# Schematic_openbook_v56.net
KiCad netlist of a schematic drawn in EAGLE
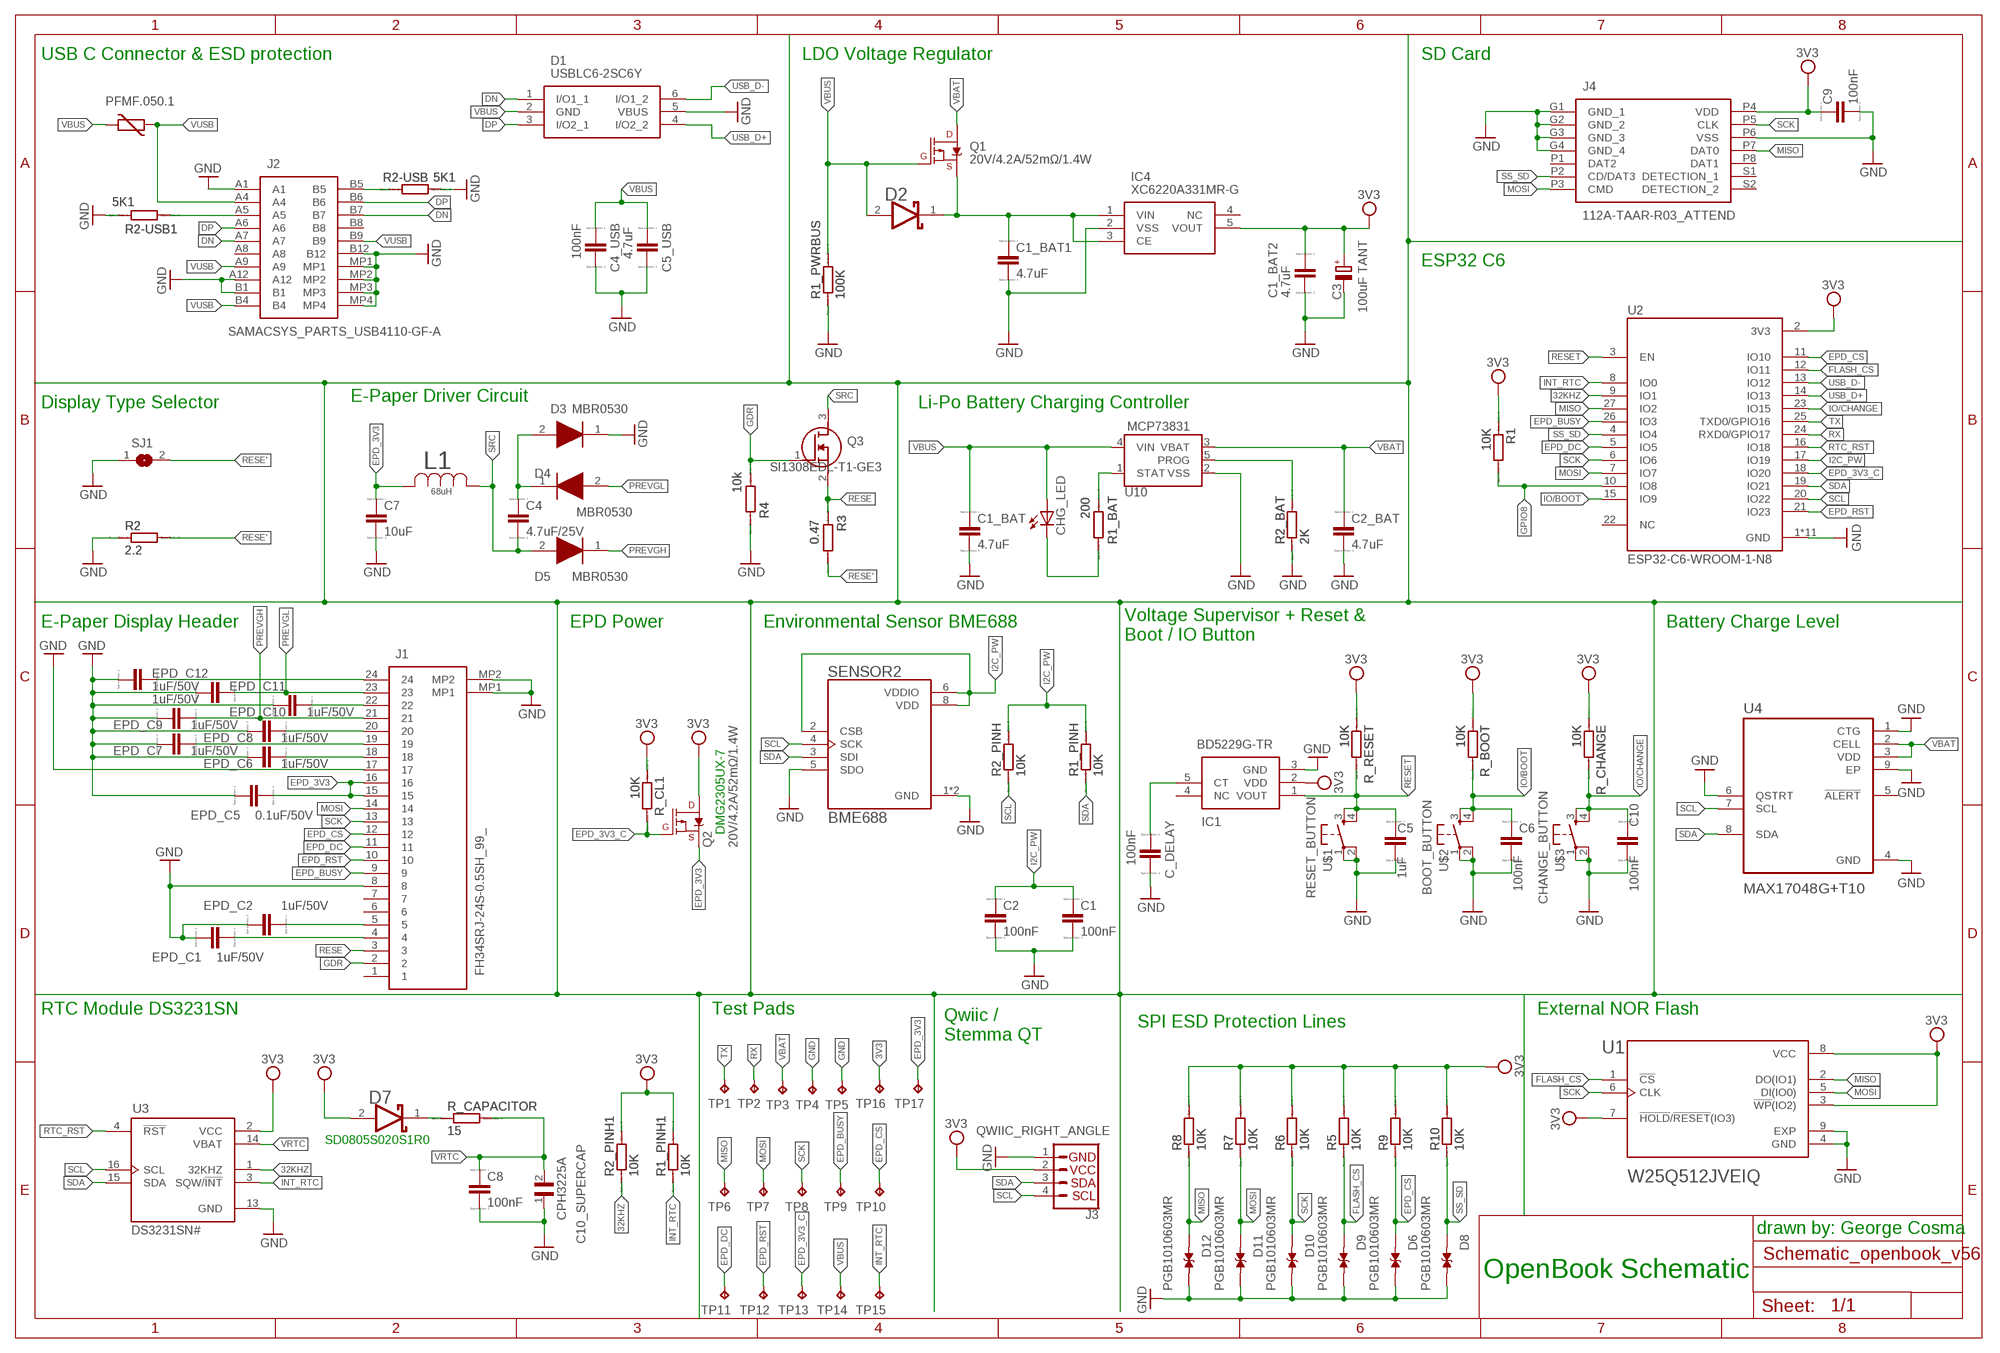
[diagram p0: schematic, sheet 1]

(export (version "E")
  (design (tool "Eeschema 10.0.6"))
  (components
    (comp (ref "C1")
      (value "100nF")
      (footprint "eagle-import:EAGLE-LTSPICE_C0402")
      (libsource (lib "eagle-import") (part "EAGLE-LTSPICE_CC0402"))
    )
    (comp (ref "C1_BAT")
      (value "4.7uF")
      (footprint "eagle-import:EAGLE-LTSPICE_C0402")
      (libsource (lib "eagle-import") (part "EAGLE-LTSPICE_CC0402"))
    )
    (comp (ref "C1_BAT1")
      (value "4.7uF")
      (footprint "eagle-import:EAGLE-LTSPICE_C0402")
      (libsource (lib "eagle-import") (part "EAGLE-LTSPICE_CC0402"))
    )
    (comp (ref "C1_BAT2")
      (value "4.7uF")
      (footprint "eagle-import:EAGLE-LTSPICE_C0402")
      (libsource (lib "eagle-import") (part "EAGLE-LTSPICE_CC0402"))
    )
    (comp (ref "C2")
      (value "100nF")
      (footprint "eagle-import:EAGLE-LTSPICE_C0402")
      (libsource (lib "eagle-import") (part "EAGLE-LTSPICE_CC0402"))
    )
    (comp (ref "C2_BAT")
      (value "4.7uF")
      (footprint "eagle-import:EAGLE-LTSPICE_C0402")
      (libsource (lib "eagle-import") (part "EAGLE-LTSPICE_CC0402"))
    )
    (comp (ref "C3")
      (value "100uF TANT")
      (footprint "eagle-import:RCL_CT3528")
      (libsource (lib "eagle-import") (part "RCL_CPOL-EUCT3528"))
    )
    (comp (ref "C4")
      (value "4.7uF/25V")
      (footprint "eagle-import:EAGLE-LTSPICE_C0402")
      (libsource (lib "eagle-import") (part "EAGLE-LTSPICE_CC0402"))
    )
    (comp (ref "C4_USB")
      (value "100nF")
      (footprint "eagle-import:EAGLE-LTSPICE_C0402")
      (libsource (lib "eagle-import") (part "EAGLE-LTSPICE_CC0402"))
    )
    (comp (ref "C5")
      (value "1uF")
      (footprint "eagle-import:EAGLE-LTSPICE_C0402")
      (libsource (lib "eagle-import") (part "EAGLE-LTSPICE_CC0402"))
    )
    (comp (ref "C5_USB")
      (value "4.7uF")
      (footprint "eagle-import:EAGLE-LTSPICE_C0402")
      (libsource (lib "eagle-import") (part "EAGLE-LTSPICE_CC0402"))
    )
    (comp (ref "C6")
      (value "100nF")
      (footprint "eagle-import:EAGLE-LTSPICE_C0402")
      (libsource (lib "eagle-import") (part "EAGLE-LTSPICE_CC0402"))
    )
    (comp (ref "C7")
      (value "10uF")
      (footprint "eagle-import:EAGLE-LTSPICE_C0402")
      (libsource (lib "eagle-import") (part "EAGLE-LTSPICE_CC0402"))
    )
    (comp (ref "C8")
      (value "100nF")
      (footprint "eagle-import:EAGLE-LTSPICE_C0402")
      (libsource (lib "eagle-import") (part "EAGLE-LTSPICE_CC0402"))
    )
    (comp (ref "C9")
      (value "100nF")
      (footprint "eagle-import:EAGLE-LTSPICE_C0402")
      (libsource (lib "eagle-import") (part "EAGLE-LTSPICE_CC0402"))
    )
    (comp (ref "C10")
      (value "100nF")
      (footprint "eagle-import:EAGLE-LTSPICE_C0402")
      (libsource (lib "eagle-import") (part "EAGLE-LTSPICE_CC0402"))
    )
    (comp (ref "C10_SUPERCAP")
      (value "CPH3225A")
      (footprint "eagle-import:CAPCP3225X100N")
      (fields (field (name "MF") "Seiko Instruments"))
      (libsource (lib "eagle-import") (part "CPH3225A"))
    )
    (comp (ref "CHG_LED")
      (value "ADAFRUIT_LEDCHIP-LED0603")
      (footprint "eagle-import:ADAFRUIT_CHIP-LED0603")
      (libsource (lib "eagle-import") (part "ADAFRUIT_LEDCHIP-LED0603"))
    )
    (comp (ref "C_DELAY")
      (value "100nF")
      (footprint "eagle-import:EAGLE-LTSPICE_C0402")
      (libsource (lib "eagle-import") (part "EAGLE-LTSPICE_CC0402"))
    )
    (comp (ref "D1")
      (value "USBLC6-2SC6Y")
      (footprint "eagle-import:SOT95P280X145-6N")
      (fields (field (name "MF") "STMicroelectronics"))
      (libsource (lib "eagle-import") (part "USBLC6-2SC6Y"))
    )
    (comp (ref "D2")
      (value "ESP32_WROVER_AVX---SD0805S020S1R0_AVX_SD0805S020S1R0_0_0AVX_SD0805S020S1R0_0_0")
      (footprint "eagle-import:ESP32_WROVER_AVX---SD0805S020S1R0_AVX_SD0805S020S1R0_0")
      (fields
        (field (name "DIGIKEY_PART_NUMBER") "478-7800-1-ND")
        (field (name "MF") "AVX")
        (field (name "MOUSER_PART_NUMBER") "581-SD0805S020S1R0")
      )
      (libsource (lib "eagle-import") (part "ESP32_WROVER_AVX---SD0805S020S1R0_AVX_SD0805S020S1R0_0_0AVX_SD0805S020S1R0_0_0"))
    )
    (comp (ref "D3")
      (value "MBR0530")
      (footprint "eagle-import:SOD3716X135N")
      (fields (field (name "MF") "ON Semiconductor"))
      (libsource (lib "eagle-import") (part "MBR0530"))
    )
    (comp (ref "D4")
      (value "MBR0530")
      (footprint "eagle-import:SOD3716X135N")
      (fields (field (name "MF") "ON Semiconductor"))
      (libsource (lib "eagle-import") (part "MBR0530"))
    )
    (comp (ref "D5")
      (value "MBR0530")
      (footprint "eagle-import:SOD3716X135N")
      (fields (field (name "MF") "ON Semiconductor"))
      (libsource (lib "eagle-import") (part "MBR0530"))
    )
    (comp (ref "D6")
      (value "PGB1010603MR")
      (footprint "eagle-import:DIOC1608X36N")
      (fields (field (name "MF") "Littelfuse Inc."))
      (libsource (lib "eagle-import") (part "PGB1010603MR"))
    )
    (comp (ref "D7")
      (value "SD0805S020S1R0")
      (footprint "eagle-import:ESP32_WROVER_AVX---SD0805S020S1R0_AVX_SD0805S020S1R0_0")
      (fields
        (field (name "DIGIKEY_PART_NUMBER") "478-7800-1-ND")
        (field (name "MF") "AVX")
        (field (name "MOUSER_PART_NUMBER") "581-SD0805S020S1R0")
      )
      (libsource (lib "eagle-import") (part "ESP32_WROVER_AVX---SD0805S020S1R0_AVX_SD0805S020S1R0_0_0AVX_SD0805S020S1R0_0_0"))
    )
    (comp (ref "D8")
      (value "PGB1010603MR")
      (footprint "eagle-import:DIOC1608X36N")
      (fields (field (name "MF") "Littelfuse Inc."))
      (libsource (lib "eagle-import") (part "PGB1010603MR"))
    )
    (comp (ref "D9")
      (value "PGB1010603MR")
      (footprint "eagle-import:DIOC1608X36N")
      (fields (field (name "MF") "Littelfuse Inc."))
      (libsource (lib "eagle-import") (part "PGB1010603MR"))
    )
    (comp (ref "D10")
      (value "PGB1010603MR")
      (footprint "eagle-import:DIOC1608X36N")
      (fields (field (name "MF") "Littelfuse Inc."))
      (libsource (lib "eagle-import") (part "PGB1010603MR"))
    )
    (comp (ref "D11")
      (value "PGB1010603MR")
      (footprint "eagle-import:DIOC1608X36N")
      (fields (field (name "MF") "Littelfuse Inc."))
      (libsource (lib "eagle-import") (part "PGB1010603MR"))
    )
    (comp (ref "D12")
      (value "PGB1010603MR")
      (footprint "eagle-import:DIOC1608X36N")
      (fields (field (name "MF") "Littelfuse Inc."))
      (libsource (lib "eagle-import") (part "PGB1010603MR"))
    )
    (comp (ref "EPD_C1")
      (value "1uF/50V")
      (footprint "eagle-import:EAGLE-LTSPICE_C0402")
      (libsource (lib "eagle-import") (part "EAGLE-LTSPICE_CC0402"))
    )
    (comp (ref "EPD_C2")
      (value "1uF/50V")
      (footprint "eagle-import:EAGLE-LTSPICE_C0402")
      (libsource (lib "eagle-import") (part "EAGLE-LTSPICE_CC0402"))
    )
    (comp (ref "EPD_C5")
      (value "0.1uF/50V")
      (footprint "eagle-import:EAGLE-LTSPICE_C0402")
      (libsource (lib "eagle-import") (part "EAGLE-LTSPICE_CC0402"))
    )
    (comp (ref "EPD_C6")
      (value "1uF/50V")
      (footprint "eagle-import:EAGLE-LTSPICE_C0402")
      (libsource (lib "eagle-import") (part "EAGLE-LTSPICE_CC0402"))
    )
    (comp (ref "EPD_C7")
      (value "1uF/50V")
      (footprint "eagle-import:EAGLE-LTSPICE_C0402")
      (libsource (lib "eagle-import") (part "EAGLE-LTSPICE_CC0402"))
    )
    (comp (ref "EPD_C8")
      (value "1uF/50V")
      (footprint "eagle-import:EAGLE-LTSPICE_C0402")
      (libsource (lib "eagle-import") (part "EAGLE-LTSPICE_CC0402"))
    )
    (comp (ref "EPD_C9")
      (value "1uF/50V")
      (footprint "eagle-import:EAGLE-LTSPICE_C0402")
      (libsource (lib "eagle-import") (part "EAGLE-LTSPICE_CC0402"))
    )
    (comp (ref "EPD_C10")
      (value "1uF/50V")
      (footprint "eagle-import:EAGLE-LTSPICE_C0402")
      (libsource (lib "eagle-import") (part "EAGLE-LTSPICE_CC0402"))
    )
    (comp (ref "EPD_C11")
      (value "1uF/50V")
      (footprint "eagle-import:EAGLE-LTSPICE_C0402")
      (libsource (lib "eagle-import") (part "EAGLE-LTSPICE_CC0402"))
    )
    (comp (ref "EPD_C12")
      (value "1uF/50V")
      (footprint "eagle-import:EAGLE-LTSPICE_C0402")
      (libsource (lib "eagle-import") (part "EAGLE-LTSPICE_CC0402"))
    )
    (comp (ref "IC1")
      (value "BD5229G-TR")
      (footprint "eagle-import:SOT95P280X125-5N")
      (fields (field (name "MOUSER_PART_NUMBER") "755-BD5229G-TR"))
      (libsource (lib "eagle-import") (part "BD5229G-TR"))
    )
    (comp (ref "IC4")
      (value "XC6220A331MR-G")
      (footprint "eagle-import:SOT95P280X120-5N")
      (fields (field (name "MOUSER_PART_NUMBER") "865-XC6220A331MR-G"))
      (libsource (lib "eagle-import") (part "XC6220A331MR-G"))
    )
    (comp (ref "J1")
      (value "FH34SRJ-24S-0.5SH_99_")
      (footprint "eagle-import:FH34SRJ24S05SH99")
      (fields
        (field (name "MANUFACTURER_PART_NUMBER") "FH34SRJ-24S-0.5SH(99)")
        (field (name "MOUSER_PART_NUMBER") "798-FH34SRJ24S05SH99")
      )
      (libsource (lib "eagle-import") (part "FH34SRJ-24S-0.5SH_99_"))
    )
    (comp (ref "J2")
      (value "SAMACSYS_PARTS_USB4110-GF-A")
      (footprint "eagle-import:SAMACSYS_PARTS_USB4110GFA")
      (fields
        (field (name "MANUFACTURER_PART_NUMBER") "USB4110-GF-A")
        (field (name "MOUSER_PART_NUMBER") "640-USB4110-GF-A")
      )
      (libsource (lib "eagle-import") (part "SAMACSYS_PARTS_USB4110-GF-A"))
    )
    (comp (ref "J3")
      (value "QWIIC_RIGHT_ANGLE")
      (footprint "eagle-import:JST04_1MM_RA")
      (libsource (lib "eagle-import") (part "QWIIC_CONNECTORJS-1MM"))
    )
    (comp (ref "J4")
      (value "112A-TAAR-R03_ATTEND")
      (footprint "eagle-import:112ATAARR03ATTEND")
      (fields (field (name "MANUFACTURER_PART_NUMBER") "112A-TAAR-R03 ATTEND"))
      (libsource (lib "eagle-import") (part "112A-TAAR-R03_ATTEND"))
    )
    (comp (ref "L1")
      (value "68uH")
      (footprint "eagle-import:IND_4828-WE-TPC_WRE")
      (fields
        (field (name "MANUFACTURER_PART_NUMBER") "744043680")
        (field (name "COPYRIGHT") "Copyright (C) 2024 Ultra Librarian. All rights reserved.")
      )
      (libsource (lib "eagle-import") (part "744043680IND_4828-WE-TPC_WRE"))
    )
    (comp (ref "PFMF.050.1")
      (value "ESP32C6_VARISTORCN1812")
      (footprint "eagle-import:ESP32C6_VARISTOR_CT_CN1812")
      (libsource (lib "eagle-import") (part "ESP32C6_VARISTORCN1812"))
    )
    (comp (ref "Q1")
      (value "20V/4.2A/52mΩ/1.4W")
      (footprint "eagle-import:ESP32_WROVER_SPARKFUN-DISCRETESEMI_SOT23-3")
      (libsource (lib "eagle-import") (part "ESP32_WROVER_SPARKFUN-DISCRETESEMI_MOSFET_PCH-DMG2305UX-7"))
    )
    (comp (ref "Q2")
      (value "20V/4.2A/52mΩ/1.4W")
      (footprint "eagle-import:ESP32_WROVER_SPARKFUN-DISCRETESEMI_SOT23-3")
      (libsource (lib "eagle-import") (part "ESP32_WROVER_SPARKFUN-DISCRETESEMI_MOSFET_PCH-DMG2305UX-7"))
    )
    (comp (ref "Q3")
      (value "SI1308EDL-T1-GE3")
      (footprint "eagle-import:SOT65P210X110-3N")
      (fields (field (name "MF") "Vishay Siliconix"))
      (libsource (lib "eagle-import") (part "SI1308EDL-T1-GE3"))
    )
    (comp (ref "R1")
      (value "10K")
      (footprint "eagle-import:ESP32_WROVER_EAGLE-LTSPICE_R0402")
      (libsource (lib "eagle-import") (part "ESP32_WROVER_EAGLE-LTSPICE_RR0402"))
    )
    (comp (ref "R1_BAT")
      (value "200")
      (footprint "eagle-import:ESP32_WROVER_EAGLE-LTSPICE_R0402")
      (libsource (lib "eagle-import") (part "ESP32_WROVER_EAGLE-LTSPICE_RR0402"))
    )
    (comp (ref "R1_PINH")
      (value "10K")
      (footprint "eagle-import:ESP32_WROVER_EAGLE-LTSPICE_R0402")
      (libsource (lib "eagle-import") (part "ESP32_WROVER_EAGLE-LTSPICE_RR0402"))
    )
    (comp (ref "R1_PINH1")
      (value "10K")
      (footprint "eagle-import:ESP32_WROVER_EAGLE-LTSPICE_R0402")
      (libsource (lib "eagle-import") (part "ESP32_WROVER_EAGLE-LTSPICE_RR0402"))
    )
    (comp (ref "R1_PWRBUS")
      (value "100K")
      (footprint "eagle-import:ESP32_WROVER_EAGLE-LTSPICE_R0402")
      (libsource (lib "eagle-import") (part "ESP32_WROVER_EAGLE-LTSPICE_RR0402"))
    )
    (comp (ref "R2")
      (value "2.2")
      (footprint "eagle-import:ESP32_WROVER_EAGLE-LTSPICE_R0402")
      (libsource (lib "eagle-import") (part "ESP32_WROVER_EAGLE-LTSPICE_RR0402"))
    )
    (comp (ref "R2-USB")
      (value "5K1")
      (footprint "eagle-import:ESP32_WROVER_EAGLE-LTSPICE_R0402")
      (libsource (lib "eagle-import") (part "ESP32_WROVER_EAGLE-LTSPICE_RR0402"))
    )
    (comp (ref "R2-USB1")
      (value "5K1")
      (footprint "eagle-import:ESP32_WROVER_EAGLE-LTSPICE_R0402")
      (libsource (lib "eagle-import") (part "ESP32_WROVER_EAGLE-LTSPICE_RR0402"))
    )
    (comp (ref "R2_BAT")
      (value "2K")
      (footprint "eagle-import:ESP32_WROVER_EAGLE-LTSPICE_R0402")
      (libsource (lib "eagle-import") (part "ESP32_WROVER_EAGLE-LTSPICE_RR0402"))
    )
    (comp (ref "R2_PINH")
      (value "10K")
      (footprint "eagle-import:ESP32_WROVER_EAGLE-LTSPICE_R0402")
      (libsource (lib "eagle-import") (part "ESP32_WROVER_EAGLE-LTSPICE_RR0402"))
    )
    (comp (ref "R2_PINH1")
      (value "10K")
      (footprint "eagle-import:ESP32_WROVER_EAGLE-LTSPICE_R0402")
      (libsource (lib "eagle-import") (part "ESP32_WROVER_EAGLE-LTSPICE_RR0402"))
    )
    (comp (ref "R3")
      (value "0.47")
      (footprint "eagle-import:ESP32_WROVER_EAGLE-LTSPICE_R0402")
      (libsource (lib "eagle-import") (part "ESP32_WROVER_EAGLE-LTSPICE_RR0402"))
    )
    (comp (ref "R4")
      (value "10k")
      (footprint "eagle-import:ESP32_WROVER_EAGLE-LTSPICE_R0402")
      (libsource (lib "eagle-import") (part "ESP32_WROVER_EAGLE-LTSPICE_RR0402"))
    )
    (comp (ref "R5")
      (value "10K")
      (footprint "eagle-import:ESP32_WROVER_EAGLE-LTSPICE_R0402")
      (libsource (lib "eagle-import") (part "ESP32_WROVER_EAGLE-LTSPICE_RR0402"))
    )
    (comp (ref "R6")
      (value "10K")
      (footprint "eagle-import:ESP32_WROVER_EAGLE-LTSPICE_R0402")
      (libsource (lib "eagle-import") (part "ESP32_WROVER_EAGLE-LTSPICE_RR0402"))
    )
    (comp (ref "R7")
      (value "10K")
      (footprint "eagle-import:ESP32_WROVER_EAGLE-LTSPICE_R0402")
      (libsource (lib "eagle-import") (part "ESP32_WROVER_EAGLE-LTSPICE_RR0402"))
    )
    (comp (ref "R8")
      (value "10K")
      (footprint "eagle-import:ESP32_WROVER_EAGLE-LTSPICE_R0402")
      (libsource (lib "eagle-import") (part "ESP32_WROVER_EAGLE-LTSPICE_RR0402"))
    )
    (comp (ref "R9")
      (value "10K")
      (footprint "eagle-import:ESP32_WROVER_EAGLE-LTSPICE_R0402")
      (libsource (lib "eagle-import") (part "ESP32_WROVER_EAGLE-LTSPICE_RR0402"))
    )
    (comp (ref "R10")
      (value "10K")
      (footprint "eagle-import:ESP32_WROVER_EAGLE-LTSPICE_R0402")
      (libsource (lib "eagle-import") (part "ESP32_WROVER_EAGLE-LTSPICE_RR0402"))
    )
    (comp (ref "R_BOOT")
      (value "10K")
      (footprint "eagle-import:ESP32_WROVER_EAGLE-LTSPICE_R0402")
      (libsource (lib "eagle-import") (part "ESP32_WROVER_EAGLE-LTSPICE_RR0402"))
    )
    (comp (ref "R_CAPACITOR")
      (value "15")
      (footprint "eagle-import:ESP32_WROVER_EAGLE-LTSPICE_R0402")
      (libsource (lib "eagle-import") (part "ESP32_WROVER_EAGLE-LTSPICE_RR0402"))
    )
    (comp (ref "R_CHANGE")
      (value "10K")
      (footprint "eagle-import:ESP32_WROVER_EAGLE-LTSPICE_R0402")
      (libsource (lib "eagle-import") (part "ESP32_WROVER_EAGLE-LTSPICE_RR0402"))
    )
    (comp (ref "R_CL1")
      (value "10K")
      (footprint "eagle-import:ESP32_WROVER_EAGLE-LTSPICE_R0402")
      (libsource (lib "eagle-import") (part "ESP32_WROVER_EAGLE-LTSPICE_RR0402"))
    )
    (comp (ref "R_RESET")
      (value "10K")
      (footprint "eagle-import:ESP32_WROVER_EAGLE-LTSPICE_R0402")
      (libsource (lib "eagle-import") (part "ESP32_WROVER_EAGLE-LTSPICE_RR0402"))
    )
    (comp (ref "SENSOR2")
      (value "BME688")
      (footprint "eagle-import:ESP32_WROVER_BME680_PSON80P300X300X100-8N")
      (fields (field (name "MF") "Bosch Sensortec") (field (name "MP") "BME680"))
      (libsource (lib "eagle-import") (part "ESP32_WROVER_BME680_BME680"))
    )
    (comp (ref "SJ1") (value "SJ") (footprint "eagle-import:SJ") (libsource (lib "eagle-import") (part "SJ")))
    (comp (ref "TP1")
      (value "TPTP20R")
      (footprint "eagle-import:TP20R")
      (libsource (lib "eagle-import") (part "TPTP20R"))
    )
    (comp (ref "TP2")
      (value "TPTP20R")
      (footprint "eagle-import:TP20R")
      (libsource (lib "eagle-import") (part "TPTP20R"))
    )
    (comp (ref "TP3")
      (value "TPTP20R")
      (footprint "eagle-import:TP20R")
      (libsource (lib "eagle-import") (part "TPTP20R"))
    )
    (comp (ref "TP4")
      (value "TPTP20R")
      (footprint "eagle-import:TP20R")
      (libsource (lib "eagle-import") (part "TPTP20R"))
    )
    (comp (ref "TP5")
      (value "TPTP20R")
      (footprint "eagle-import:TP20R")
      (libsource (lib "eagle-import") (part "TPTP20R"))
    )
    (comp (ref "TP6")
      (value "TPTP20R")
      (footprint "eagle-import:TP20R")
      (libsource (lib "eagle-import") (part "TPTP20R"))
    )
    (comp (ref "TP7")
      (value "TPTP20R")
      (footprint "eagle-import:TP20R")
      (libsource (lib "eagle-import") (part "TPTP20R"))
    )
    (comp (ref "TP8")
      (value "TPTP20R")
      (footprint "eagle-import:TP20R")
      (libsource (lib "eagle-import") (part "TPTP20R"))
    )
    (comp (ref "TP9")
      (value "TPTP20R")
      (footprint "eagle-import:TP20R")
      (libsource (lib "eagle-import") (part "TPTP20R"))
    )
    (comp (ref "TP10")
      (value "TPTP20R")
      (footprint "eagle-import:TP20R")
      (libsource (lib "eagle-import") (part "TPTP20R"))
    )
    (comp (ref "TP11")
      (value "TPTP20R")
      (footprint "eagle-import:TP20R")
      (libsource (lib "eagle-import") (part "TPTP20R"))
    )
    (comp (ref "TP12")
      (value "TPTP20R")
      (footprint "eagle-import:TP20R")
      (libsource (lib "eagle-import") (part "TPTP20R"))
    )
    (comp (ref "TP13")
      (value "TPTP20R")
      (footprint "eagle-import:TP20R")
      (libsource (lib "eagle-import") (part "TPTP20R"))
    )
    (comp (ref "TP14")
      (value "TPTP20R")
      (footprint "eagle-import:TP20R")
      (libsource (lib "eagle-import") (part "TPTP20R"))
    )
    (comp (ref "TP15")
      (value "TPTP20R")
      (footprint "eagle-import:TP20R")
      (libsource (lib "eagle-import") (part "TPTP20R"))
    )
    (comp (ref "TP16")
      (value "TPTP20R")
      (footprint "eagle-import:TP20R")
      (libsource (lib "eagle-import") (part "TPTP20R"))
    )
    (comp (ref "TP17")
      (value "TPTP20R")
      (footprint "eagle-import:TP20R")
      (libsource (lib "eagle-import") (part "TPTP20R"))
    )
    (comp (ref "U$1")
      (value "RESET_BUTTON")
      (footprint "eagle-import:MYBUTTON")
      (libsource (lib "eagle-import") (part "BUTTON_CUSYOMV1"))
    )
    (comp (ref "U$2")
      (value "BOOT_BUTTON")
      (footprint "eagle-import:MYBUTTON")
      (libsource (lib "eagle-import") (part "BUTTON_CUSYOMV1"))
    )
    (comp (ref "U$3")
      (value "CHANGE_BUTTON")
      (footprint "eagle-import:MYBUTTON")
      (libsource (lib "eagle-import") (part "BUTTON_CUSYOMV1"))
    )
    (comp (ref "U1")
      (value "W25Q512JVEIQ")
      (footprint "eagle-import:SON127P600X800X80-9N")
      (fields (field (name "MF") "Winbond Electronics"))
      (libsource (lib "eagle-import") (part "W25Q512JVEIQ"))
    )
    (comp (ref "U2")
      (value "ESP32-C6-WROOM-1-N8")
      (footprint "eagle-import:XCVR_ESP32-C6-WROOM-1-N8")
      (fields (field (name "MF") "Espressif Systems"))
      (libsource (lib "eagle-import") (part "ESP32-C6-WROOM-1-N8"))
    )
    (comp (ref "U3")
      (value "DS3231SN#")
      (footprint "eagle-import:SOIC127P1032X265-16N")
      (fields (field (name "MF") "Analog Devices"))
      (libsource (lib "eagle-import") (part "DS3231SN#"))
    )
    (comp (ref "U4")
      (value "MAX17048G+T10")
      (footprint "eagle-import:SON50P200X200X80-9N")
      (fields (field (name "MF") "Analog Devices"))
      (libsource (lib "eagle-import") (part "MAX17048G+T10"))
    )
    (comp (ref "U10")
      (value "MCP73831")
      (footprint "eagle-import:ESP32_WROVER_SPARKFUN-IC-POWER_SOT23-5")
      (libsource (lib "eagle-import") (part "ESP32_WROVER_SPARKFUN-IC-POWER_MCP73831"))
    )
  )
  (nets
    (net (code "1") (name "3V3") (class "Default")
      (node (ref "C1_BAT2") (pin "1") (pinfunction "1_1") (pintype "passive"))
      (node (ref "C3") (pin "+") (pinfunction "+_+") (pintype "passive"))
      (node (ref "C9") (pin "1") (pinfunction "1_1") (pintype "passive"))
      (node (ref "D7") (pin "2") (pinfunction "ANODE_2") (pintype "bidirectional"))
      (node (ref "IC1") (pin "2") (pinfunction "VDD_2") (pintype "bidirectional"))
      (node (ref "IC4") (pin "5") (pinfunction "VOUT_5") (pintype "bidirectional"))
      (node (ref "J3") (pin "2") (pinfunction "2_2") (pintype "power_in"))
      (node (ref "J4") (pin "P4") (pinfunction "VDD_P4") (pintype "bidirectional"))
      (node (ref "Q2") (pin "3") (pinfunction "D_3") (pintype "bidirectional"))
      (node (ref "R1") (pin "1") (pinfunction "1_1") (pintype "passive"))
      (node (ref "R10") (pin "2") (pinfunction "2_2") (pintype "passive"))
      (node (ref "R1_PINH1") (pin "2") (pinfunction "2_2") (pintype "passive"))
      (node (ref "R2_PINH1") (pin "2") (pinfunction "2_2") (pintype "passive"))
      (node (ref "R5") (pin "2") (pinfunction "2_2") (pintype "passive"))
      (node (ref "R6") (pin "2") (pinfunction "2_2") (pintype "passive"))
      (node (ref "R7") (pin "2") (pinfunction "2_2") (pintype "passive"))
      (node (ref "R8") (pin "2") (pinfunction "2_2") (pintype "passive"))
      (node (ref "R9") (pin "2") (pinfunction "2_2") (pintype "passive"))
      (node (ref "R_BOOT") (pin "1") (pinfunction "1_1") (pintype "passive"))
      (node (ref "R_CHANGE") (pin "1") (pinfunction "1_1") (pintype "passive"))
      (node (ref "R_CL1") (pin "1") (pinfunction "1_1") (pintype "passive"))
      (node (ref "R_RESET") (pin "1") (pinfunction "1_1") (pintype "passive"))
      (node (ref "TP16") (pin "TP") (pinfunction "TP_TP") (pintype "input"))
      (node (ref "U1") (pin "3") (pinfunction "~{WP}(IO2)_3") (pintype "bidirectional"))
      (node (ref "U1") (pin "7") (pinfunction "~{HOLD}/~{RESET}(IO3)_7") (pintype "bidirectional"))
      (node (ref "U1") (pin "8") (pinfunction "VCC_8") (pintype "power_in"))
      (node (ref "U2") (pin "2") (pinfunction "3V3_2") (pintype "power_in"))
      (node (ref "U3") (pin "2") (pinfunction "VCC_2") (pintype "power_in"))
    )
    (net (code "2") (name "32KHZ") (class "Default")
      (node (ref "R2_PINH1") (pin "1") (pinfunction "1_1") (pintype "passive"))
      (node (ref "U2") (pin "9") (pinfunction "IO1_9") (pintype "bidirectional"))
      (node (ref "U3") (pin "1") (pinfunction "32KHZ_1") (pintype "output"))
    )
    (net (code "3") (name "DN") (class "Default")
      (node (ref "D1") (pin "1") (pinfunction "I/O1_1_1") (pintype "bidirectional"))
      (node (ref "J2") (pin "A7") (pinfunction "A7_A7") (pintype "bidirectional"))
      (node (ref "J2") (pin "B7") (pinfunction "B7_B7") (pintype "bidirectional"))
    )
    (net (code "4") (name "DP") (class "Default")
      (node (ref "D1") (pin "3") (pinfunction "I/O2_1_3") (pintype "bidirectional"))
      (node (ref "J2") (pin "A6") (pinfunction "A6_A6") (pintype "bidirectional"))
      (node (ref "J2") (pin "B6") (pinfunction "B6_B6") (pintype "bidirectional"))
    )
    (net (code "5") (name "EPD_3V3") (class "Default")
      (node (ref "C7") (pin "1") (pinfunction "1_1") (pintype "passive"))
      (node (ref "EPD_C5") (pin "1") (pinfunction "1_1") (pintype "passive"))
      (node (ref "J1") (pin "15") (pinfunction "15_15") (pintype "bidirectional"))
      (node (ref "J1") (pin "16") (pinfunction "16_16") (pintype "bidirectional"))
      (node (ref "L1") (pin "2") (pinfunction "2_2") (pintype "passive"))
      (node (ref "Q2") (pin "2") (pinfunction "S_2") (pintype "bidirectional"))
      (node (ref "TP17") (pin "TP") (pinfunction "TP_TP") (pintype "input"))
    )
    (net (code "6") (name "EPD_3V3_C") (class "Default")
      (node (ref "Q2") (pin "1") (pinfunction "G_1") (pintype "bidirectional"))
      (node (ref "R_CL1") (pin "2") (pinfunction "2_2") (pintype "passive"))
      (node (ref "TP13") (pin "TP") (pinfunction "TP_TP") (pintype "input"))
      (node (ref "U2") (pin "18") (pinfunction "IO20_18") (pintype "bidirectional"))
    )
    (net (code "7") (name "EPD_BUSY") (class "Default")
      (node (ref "J1") (pin "9") (pinfunction "9_9") (pintype "bidirectional"))
      (node (ref "TP9") (pin "TP") (pinfunction "TP_TP") (pintype "input"))
      (node (ref "U2") (pin "26") (pinfunction "IO3_26") (pintype "bidirectional"))
    )
    (net (code "8") (name "EPD_CS") (class "Default")
      (node (ref "D6") (pin "1") (pinfunction "1_1") (pintype "passive"))
      (node (ref "J1") (pin "12") (pinfunction "12_12") (pintype "bidirectional"))
      (node (ref "R9") (pin "1") (pinfunction "1_1") (pintype "passive"))
      (node (ref "TP10") (pin "TP") (pinfunction "TP_TP") (pintype "input"))
      (node (ref "U2") (pin "11") (pinfunction "IO10_11") (pintype "bidirectional"))
    )
    (net (code "9") (name "EPD_DC") (class "Default")
      (node (ref "J1") (pin "11") (pinfunction "11_11") (pintype "bidirectional"))
      (node (ref "TP11") (pin "TP") (pinfunction "TP_TP") (pintype "input"))
      (node (ref "U2") (pin "5") (pinfunction "IO5_5") (pintype "bidirectional"))
    )
    (net (code "10") (name "EPD_RST") (class "Default")
      (node (ref "J1") (pin "10") (pinfunction "10_10") (pintype "bidirectional"))
      (node (ref "TP12") (pin "TP") (pinfunction "TP_TP") (pintype "input"))
      (node (ref "U2") (pin "21") (pinfunction "IO23_21") (pintype "bidirectional"))
    )
    (net (code "11") (name "FLASH_CS") (class "Default")
      (node (ref "D9") (pin "1") (pinfunction "1_1") (pintype "passive"))
      (node (ref "R5") (pin "1") (pinfunction "1_1") (pintype "passive"))
      (node (ref "U1") (pin "1") (pinfunction "~{CS}_1") (pintype "input"))
      (node (ref "U2") (pin "12") (pinfunction "IO11_12") (pintype "bidirectional"))
    )
    (net (code "12") (name "GDR") (class "Default")
      (node (ref "J1") (pin "2") (pinfunction "2_2") (pintype "bidirectional"))
      (node (ref "Q3") (pin "1") (pinfunction "G_1") (pintype "bidirectional"))
      (node (ref "R4") (pin "2") (pinfunction "2_2") (pintype "passive"))
    )
    (net (code "13") (name "GND") (class "Default")
      (node (ref "C1") (pin "2") (pinfunction "2_2") (pintype "passive"))
      (node (ref "C10") (pin "2") (pinfunction "2_2") (pintype "passive"))
      (node (ref "C10_SUPERCAP") (pin "1") (pinfunction "1_1") (pintype "passive"))
      (node (ref "C1_BAT") (pin "2") (pinfunction "2_2") (pintype "passive"))
      (node (ref "C1_BAT1") (pin "2") (pinfunction "2_2") (pintype "passive"))
      (node (ref "C1_BAT2") (pin "2") (pinfunction "2_2") (pintype "passive"))
      (node (ref "C2") (pin "2") (pinfunction "2_2") (pintype "passive"))
      (node (ref "C2_BAT") (pin "2") (pinfunction "2_2") (pintype "passive"))
      (node (ref "C3") (pin "-") (pinfunction "-_-") (pintype "passive"))
      (node (ref "C4_USB") (pin "2") (pinfunction "2_2") (pintype "passive"))
      (node (ref "C5") (pin "2") (pinfunction "2_2") (pintype "passive"))
      (node (ref "C5_USB") (pin "2") (pinfunction "2_2") (pintype "passive"))
      (node (ref "C6") (pin "2") (pinfunction "2_2") (pintype "passive"))
      (node (ref "C7") (pin "2") (pinfunction "2_2") (pintype "passive"))
      (node (ref "C8") (pin "2") (pinfunction "2_2") (pintype "passive"))
      (node (ref "C9") (pin "2") (pinfunction "2_2") (pintype "passive"))
      (node (ref "C_DELAY") (pin "2") (pinfunction "2_2") (pintype "passive"))
      (node (ref "D1") (pin "5") (pinfunction "VBUS_5") (pintype "bidirectional"))
      (node (ref "D10") (pin "2") (pinfunction "2_2") (pintype "passive"))
      (node (ref "D11") (pin "2") (pinfunction "2_2") (pintype "passive"))
      (node (ref "D12") (pin "2") (pinfunction "2_2") (pintype "passive"))
      (node (ref "D4") (pin "1") (pinfunction "K_1") (pintype "bidirectional"))
      (node (ref "D6") (pin "2") (pinfunction "2_2") (pintype "passive"))
      (node (ref "D8") (pin "2") (pinfunction "2_2") (pintype "passive"))
      (node (ref "D9") (pin "2") (pinfunction "2_2") (pintype "passive"))
      (node (ref "EPD_C1") (pin "2") (pinfunction "2_2") (pintype "passive"))
      (node (ref "EPD_C10") (pin "2") (pinfunction "2_2") (pintype "passive"))
      (node (ref "EPD_C11") (pin "2") (pinfunction "2_2") (pintype "passive"))
      (node (ref "EPD_C12") (pin "2") (pinfunction "2_2") (pintype "passive"))
      (node (ref "EPD_C2") (pin "2") (pinfunction "2_2") (pintype "passive"))
      (node (ref "EPD_C5") (pin "2") (pinfunction "2_2") (pintype "passive"))
      (node (ref "EPD_C6") (pin "2") (pinfunction "2_2") (pintype "passive"))
      (node (ref "EPD_C7") (pin "2") (pinfunction "2_2") (pintype "passive"))
      (node (ref "EPD_C8") (pin "2") (pinfunction "2_2") (pintype "passive"))
      (node (ref "EPD_C9") (pin "2") (pinfunction "2_2") (pintype "passive"))
      (node (ref "IC1") (pin "3") (pinfunction "GND_3") (pintype "bidirectional"))
      (node (ref "IC4") (pin "2") (pinfunction "VSS_2") (pintype "bidirectional"))
      (node (ref "J1") (pin "17") (pinfunction "17_17") (pintype "bidirectional"))
      (node (ref "J1") (pin "8") (pinfunction "8_8") (pintype "bidirectional"))
      (node (ref "J1") (pin "MP1") (pinfunction "MP1_MP1") (pintype "bidirectional"))
      (node (ref "J1") (pin "MP2") (pinfunction "MP2_MP2") (pintype "bidirectional"))
      (node (ref "J2") (pin "A1") (pinfunction "A1_A1") (pintype "bidirectional"))
      (node (ref "J2") (pin "A12") (pinfunction "A12_A12") (pintype "bidirectional"))
      (node (ref "J2") (pin "B1") (pinfunction "B1_B1") (pintype "bidirectional"))
      (node (ref "J2") (pin "B12") (pinfunction "B12_B12") (pintype "bidirectional"))
      (node (ref "J2") (pin "MP1") (pinfunction "MP1_MP1") (pintype "bidirectional"))
      (node (ref "J2") (pin "MP2") (pinfunction "MP2_MP2") (pintype "bidirectional"))
      (node (ref "J2") (pin "MP3") (pinfunction "MP3_MP3") (pintype "bidirectional"))
      (node (ref "J2") (pin "MP4") (pinfunction "MP4_MP4") (pintype "bidirectional"))
      (node (ref "J3") (pin "1") (pinfunction "1_1") (pintype "power_in"))
      (node (ref "J4") (pin "G1") (pinfunction "GND_1_G1") (pintype "bidirectional"))
      (node (ref "J4") (pin "G2") (pinfunction "GND_2_G2") (pintype "bidirectional"))
      (node (ref "J4") (pin "G3") (pinfunction "GND_3_G3") (pintype "bidirectional"))
      (node (ref "J4") (pin "G4") (pinfunction "GND_4_G4") (pintype "bidirectional"))
      (node (ref "J4") (pin "P6") (pinfunction "VSS_P6") (pintype "bidirectional"))
      (node (ref "R1_PWRBUS") (pin "1") (pinfunction "1_1") (pintype "passive"))
      (node (ref "R2") (pin "1") (pinfunction "1_1") (pintype "passive"))
      (node (ref "R2-USB") (pin "2") (pinfunction "2_2") (pintype "passive"))
      (node (ref "R2-USB1") (pin "1") (pinfunction "1_1") (pintype "passive"))
      (node (ref "R2_BAT") (pin "1") (pinfunction "1_1") (pintype "passive"))
      (node (ref "R4") (pin "1") (pinfunction "1_1") (pintype "passive"))
      (node (ref "SENSOR2") (pin "1") (pinfunction "GND_1") (pintype "power_in"))
      (node (ref "SENSOR2") (pin "5") (pinfunction "SDO_5") (pintype "bidirectional"))
      (node (ref "SENSOR2") (pin "7") (pinfunction "GND_7") (pintype "power_in"))
      (node (ref "SJ1") (pin "1") (pinfunction "1_1") (pintype "passive"))
      (node (ref "TP4") (pin "TP") (pinfunction "TP_TP") (pintype "input"))
      (node (ref "TP5") (pin "TP") (pinfunction "TP_TP") (pintype "input"))
      (node (ref "U$1") (pin "1") (pinfunction "1_1") (pintype "passive"))
      (node (ref "U$1") (pin "2") (pinfunction "2_2") (pintype "passive"))
      (node (ref "U$2") (pin "1") (pinfunction "1_1") (pintype "passive"))
      (node (ref "U$2") (pin "2") (pinfunction "2_2") (pintype "passive"))
      (node (ref "U$3") (pin "1") (pinfunction "1_1") (pintype "passive"))
      (node (ref "U$3") (pin "2") (pinfunction "2_2") (pintype "passive"))
      (node (ref "U1") (pin "4") (pinfunction "GND_4") (pintype "power_in"))
      (node (ref "U1") (pin "9") (pinfunction "EXP_9") (pintype "passive"))
      (node (ref "U10") (pin "2") (pinfunction "VSS_2") (pintype "power_in"))
      (node (ref "U2") (pin "1") (pinfunction "GND_1") (pintype "power_in"))
      (node (ref "U2") (pin "28") (pinfunction "GND_28") (pintype "power_in"))
      (node (ref "U2") (pin "29_1") (pinfunction "GND_29_1") (pintype "power_in"))
      (node (ref "U2") (pin "29_2") (pinfunction "GND_29_2") (pintype "power_in"))
      (node (ref "U2") (pin "29_3") (pinfunction "GND_29_3") (pintype "power_in"))
      (node (ref "U2") (pin "29_4") (pinfunction "GND_29_4") (pintype "power_in"))
      (node (ref "U2") (pin "29_5") (pinfunction "GND_29_5") (pintype "power_in"))
      (node (ref "U2") (pin "29_6") (pinfunction "GND_29_6") (pintype "power_in"))
      (node (ref "U2") (pin "29_7") (pinfunction "GND_29_7") (pintype "power_in"))
      (node (ref "U2") (pin "29_8") (pinfunction "GND_29_8") (pintype "power_in"))
      (node (ref "U2") (pin "29_9") (pinfunction "GND_29_9") (pintype "power_in"))
      (node (ref "U3") (pin "13") (pinfunction "GND_13") (pintype "power_in"))
      (node (ref "U4") (pin "1") (pinfunction "CTG_1") (pintype "power_in"))
      (node (ref "U4") (pin "4") (pinfunction "GND_4") (pintype "power_in"))
      (node (ref "U4") (pin "6") (pinfunction "QSTRT_6") (pintype "input"))
      (node (ref "U4") (pin "9") (pinfunction "EP_9") (pintype "power_in"))
    )
    (net (code "14") (name "GPIO8") (class "Default")
      (node (ref "R1") (pin "2") (pinfunction "2_2") (pintype "passive"))
      (node (ref "U2") (pin "10") (pinfunction "IO8_10") (pintype "bidirectional"))
    )
    (net (code "15") (name "I2C_PW") (class "Default")
      (node (ref "C1") (pin "1") (pinfunction "1_1") (pintype "passive"))
      (node (ref "C2") (pin "1") (pinfunction "1_1") (pintype "passive"))
      (node (ref "R1_PINH") (pin "2") (pinfunction "2_2") (pintype "passive"))
      (node (ref "R2_PINH") (pin "2") (pinfunction "2_2") (pintype "passive"))
      (node (ref "SENSOR2") (pin "2") (pinfunction "CSB_2") (pintype "input"))
      (node (ref "SENSOR2") (pin "6") (pinfunction "VDDIO_6") (pintype "power_in"))
      (node (ref "SENSOR2") (pin "8") (pinfunction "VDD_8") (pintype "power_in"))
      (node (ref "U2") (pin "17") (pinfunction "IO19_17") (pintype "bidirectional"))
    )
    (net (code "16") (name "INT_RTC") (class "Default")
      (node (ref "R1_PINH1") (pin "1") (pinfunction "1_1") (pintype "passive"))
      (node (ref "TP15") (pin "TP") (pinfunction "TP_TP") (pintype "input"))
      (node (ref "U2") (pin "8") (pinfunction "IO0_8") (pintype "bidirectional"))
      (node (ref "U3") (pin "3") (pinfunction "SQW/~{INT}_3") (pintype "output"))
    )
    (net (code "17") (name "IO{slash}BOOT") (class "Default")
      (node (ref "C6") (pin "1") (pinfunction "1_1") (pintype "passive"))
      (node (ref "R_BOOT") (pin "2") (pinfunction "2_2") (pintype "passive"))
      (node (ref "U$2") (pin "3") (pinfunction "3_3") (pintype "passive"))
      (node (ref "U$2") (pin "4") (pinfunction "4_4") (pintype "passive"))
      (node (ref "U2") (pin "15") (pinfunction "IO9_15") (pintype "bidirectional"))
    )
    (net (code "18") (name "IO{slash}CHANGE") (class "Default")
      (node (ref "C10") (pin "1") (pinfunction "1_1") (pintype "passive"))
      (node (ref "R_CHANGE") (pin "2") (pinfunction "2_2") (pintype "passive"))
      (node (ref "U$3") (pin "3") (pinfunction "3_3") (pintype "passive"))
      (node (ref "U$3") (pin "4") (pinfunction "4_4") (pintype "passive"))
      (node (ref "U2") (pin "23") (pinfunction "IO15_23") (pintype "bidirectional"))
    )
    (net (code "19") (name "MISO") (class "Default")
      (node (ref "D12") (pin "1") (pinfunction "1_1") (pintype "passive"))
      (node (ref "J4") (pin "P7") (pinfunction "DAT0_P7") (pintype "bidirectional"))
      (node (ref "R8") (pin "1") (pinfunction "1_1") (pintype "passive"))
      (node (ref "TP6") (pin "TP") (pinfunction "TP_TP") (pintype "input"))
      (node (ref "U1") (pin "2") (pinfunction "DO(IO1)_2") (pintype "bidirectional"))
      (node (ref "U2") (pin "27") (pinfunction "IO2_27") (pintype "bidirectional"))
    )
    (net (code "20") (name "MOSI") (class "Default")
      (node (ref "D11") (pin "1") (pinfunction "1_1") (pintype "passive"))
      (node (ref "J1") (pin "14") (pinfunction "14_14") (pintype "bidirectional"))
      (node (ref "J4") (pin "P3") (pinfunction "CMD_P3") (pintype "bidirectional"))
      (node (ref "R7") (pin "1") (pinfunction "1_1") (pintype "passive"))
      (node (ref "TP7") (pin "TP") (pinfunction "TP_TP") (pintype "input"))
      (node (ref "U1") (pin "5") (pinfunction "DI(IO0)_5") (pintype "bidirectional"))
      (node (ref "U2") (pin "7") (pinfunction "IO7_7") (pintype "bidirectional"))
    )
    (net (code "21") (name "Net-(CHG_LED-PadC)") (class "Default")
      (node (ref "CHG_LED") (pin "C") (pinfunction "C_C") (pintype "passive"))
      (node (ref "R1_BAT") (pin "1") (pinfunction "1_1") (pintype "passive"))
    )
    (net (code "22") (name "Net-(D2-CATHODE)") (class "Default")
      (node (ref "C1_BAT1") (pin "1") (pinfunction "1_1") (pintype "passive"))
      (node (ref "D2") (pin "1") (pinfunction "CATHODE_1") (pintype "bidirectional"))
      (node (ref "IC4") (pin "1") (pinfunction "VIN_1") (pintype "bidirectional"))
      (node (ref "IC4") (pin "3") (pinfunction "CE_3") (pintype "bidirectional"))
      (node (ref "Q1") (pin "2") (pinfunction "S_2") (pintype "bidirectional"))
    )
    (net (code "23") (name "Net-(D3-K)") (class "Default")
      (node (ref "C4") (pin "1") (pinfunction "1_1") (pintype "passive"))
      (node (ref "D3") (pin "1") (pinfunction "K_1") (pintype "bidirectional"))
      (node (ref "D4") (pin "2") (pinfunction "A_2") (pintype "bidirectional"))
    )
    (net (code "24") (name "Net-(D7-CATHODE)") (class "Default")
      (node (ref "D7") (pin "1") (pinfunction "CATHODE_1") (pintype "bidirectional"))
      (node (ref "R_CAPACITOR") (pin "1") (pinfunction "1_1") (pintype "passive"))
    )
    (net (code "25") (name "Net-(EPD_C1-Pad1)") (class "Default")
      (node (ref "EPD_C1") (pin "1") (pinfunction "1_1") (pintype "passive"))
      (node (ref "J1") (pin "4") (pinfunction "4_4") (pintype "bidirectional"))
    )
    (net (code "26") (name "Net-(EPD_C2-Pad1)") (class "Default")
      (node (ref "EPD_C2") (pin "1") (pinfunction "1_1") (pintype "passive"))
      (node (ref "J1") (pin "5") (pinfunction "5_5") (pintype "bidirectional"))
    )
    (net (code "27") (name "Net-(EPD_C6-Pad1)") (class "Default")
      (node (ref "EPD_C6") (pin "1") (pinfunction "1_1") (pintype "passive"))
      (node (ref "J1") (pin "18") (pinfunction "18_18") (pintype "bidirectional"))
    )
    (net (code "28") (name "Net-(EPD_C7-Pad1)") (class "Default")
      (node (ref "EPD_C7") (pin "1") (pinfunction "1_1") (pintype "passive"))
      (node (ref "J1") (pin "19") (pinfunction "19_19") (pintype "bidirectional"))
    )
    (net (code "29") (name "Net-(EPD_C8-Pad1)") (class "Default")
      (node (ref "EPD_C8") (pin "1") (pinfunction "1_1") (pintype "passive"))
      (node (ref "J1") (pin "20") (pinfunction "20_20") (pintype "bidirectional"))
    )
    (net (code "30") (name "Net-(EPD_C10-Pad1)") (class "Default")
      (node (ref "EPD_C10") (pin "1") (pinfunction "1_1") (pintype "passive"))
      (node (ref "J1") (pin "22") (pinfunction "22_22") (pintype "bidirectional"))
    )
    (net (code "31") (name "Net-(EPD_C12-Pad1)") (class "Default")
      (node (ref "EPD_C12") (pin "1") (pinfunction "1_1") (pintype "passive"))
      (node (ref "J1") (pin "24") (pinfunction "24_24") (pintype "bidirectional"))
    )
    (net (code "32") (name "Net-(IC1-CT)") (class "Default")
      (node (ref "C_DELAY") (pin "1") (pinfunction "1_1") (pintype "passive"))
      (node (ref "IC1") (pin "5") (pinfunction "CT_5") (pintype "bidirectional"))
    )
    (net (code "33") (name "Net-(J2-PadA5)") (class "Default")
      (node (ref "J2") (pin "A5") (pinfunction "A5_A5") (pintype "bidirectional"))
      (node (ref "R2-USB1") (pin "2") (pinfunction "2_2") (pintype "passive"))
    )
    (net (code "34") (name "Net-(J2-PadB5)") (class "Default")
      (node (ref "J2") (pin "B5") (pinfunction "B5_B5") (pintype "bidirectional"))
      (node (ref "R2-USB") (pin "1") (pinfunction "1_1") (pintype "passive"))
    )
    (net (code "35") (name "Net-(U10-PROG)") (class "Default")
      (node (ref "R2_BAT") (pin "2") (pinfunction "2_2") (pintype "passive"))
      (node (ref "U10") (pin "5") (pinfunction "PROG_5") (pintype "input"))
    )
    (net (code "36") (name "Net-(U10-STAT)") (class "Default")
      (node (ref "R1_BAT") (pin "2") (pinfunction "2_2") (pintype "passive"))
      (node (ref "U10") (pin "1") (pinfunction "STAT_1") (pintype "output"))
    )
    (net (code "37") (name "PREVGH") (class "Default")
      (node (ref "D5") (pin "1") (pinfunction "K_1") (pintype "bidirectional"))
      (node (ref "EPD_C9") (pin "1") (pinfunction "1_1") (pintype "passive"))
      (node (ref "J1") (pin "21") (pinfunction "21_21") (pintype "bidirectional"))
    )
    (net (code "38") (name "PREVGL") (class "Default")
      (node (ref "D3") (pin "2") (pinfunction "A_2") (pintype "bidirectional"))
      (node (ref "EPD_C11") (pin "1") (pinfunction "1_1") (pintype "passive"))
      (node (ref "J1") (pin "23") (pinfunction "23_23") (pintype "bidirectional"))
    )
    (net (code "39") (name "RESE") (class "Default")
      (node (ref "J1") (pin "3") (pinfunction "3_3") (pintype "bidirectional"))
      (node (ref "Q3") (pin "2") (pinfunction "S_2") (pintype "bidirectional"))
      (node (ref "R3") (pin "2") (pinfunction "2_2") (pintype "passive"))
    )
    (net (code "40") (name "RESE'") (class "Default")
      (node (ref "R2") (pin "2") (pinfunction "2_2") (pintype "passive"))
      (node (ref "R3") (pin "1") (pinfunction "1_1") (pintype "passive"))
      (node (ref "SJ1") (pin "2") (pinfunction "2_2") (pintype "passive"))
    )
    (net (code "41") (name "RESET") (class "Default")
      (node (ref "C5") (pin "1") (pinfunction "1_1") (pintype "passive"))
      (node (ref "IC1") (pin "1") (pinfunction "VOUT_1") (pintype "bidirectional"))
      (node (ref "R_RESET") (pin "2") (pinfunction "2_2") (pintype "passive"))
      (node (ref "U$1") (pin "3") (pinfunction "3_3") (pintype "passive"))
      (node (ref "U$1") (pin "4") (pinfunction "4_4") (pintype "passive"))
      (node (ref "U2") (pin "3") (pinfunction "EN_3") (pintype "input"))
    )
    (net (code "42") (name "RTC_RST") (class "Default")
      (node (ref "U2") (pin "16") (pinfunction "IO18_16") (pintype "bidirectional"))
      (node (ref "U3") (pin "4") (pinfunction "~{RST}_4") (pintype "input"))
    )
    (net (code "43") (name "RX") (class "Default")
      (node (ref "TP2") (pin "TP") (pinfunction "TP_TP") (pintype "input"))
      (node (ref "U2") (pin "24") (pinfunction "RXD0/GPIO17_24") (pintype "bidirectional"))
    )
    (net (code "44") (name "SCK") (class "Default")
      (node (ref "D10") (pin "1") (pinfunction "1_1") (pintype "passive"))
      (node (ref "J1") (pin "13") (pinfunction "13_13") (pintype "bidirectional"))
      (node (ref "J4") (pin "P5") (pinfunction "CLK_P5") (pintype "bidirectional"))
      (node (ref "R6") (pin "1") (pinfunction "1_1") (pintype "passive"))
      (node (ref "TP8") (pin "TP") (pinfunction "TP_TP") (pintype "input"))
      (node (ref "U1") (pin "6") (pinfunction "CLK_6") (pintype "input"))
      (node (ref "U2") (pin "6") (pinfunction "IO6_6") (pintype "bidirectional"))
    )
    (net (code "45") (name "SCL") (class "Default")
      (node (ref "J3") (pin "4") (pinfunction "4_4") (pintype "passive"))
      (node (ref "R2_PINH") (pin "1") (pinfunction "1_1") (pintype "passive"))
      (node (ref "SENSOR2") (pin "4") (pinfunction "SCK_4") (pintype "input"))
      (node (ref "U2") (pin "20") (pinfunction "IO22_20") (pintype "bidirectional"))
      (node (ref "U3") (pin "16") (pinfunction "SCL_16") (pintype "input"))
      (node (ref "U4") (pin "7") (pinfunction "SCL_7") (pintype "input"))
    )
    (net (code "46") (name "SDA") (class "Default")
      (node (ref "J3") (pin "3") (pinfunction "3_3") (pintype "passive"))
      (node (ref "R1_PINH") (pin "1") (pinfunction "1_1") (pintype "passive"))
      (node (ref "SENSOR2") (pin "3") (pinfunction "SDI_3") (pintype "bidirectional"))
      (node (ref "U2") (pin "19") (pinfunction "IO21_19") (pintype "bidirectional"))
      (node (ref "U3") (pin "15") (pinfunction "SDA_15") (pintype "bidirectional"))
      (node (ref "U4") (pin "8") (pinfunction "SDA_8") (pintype "bidirectional"))
    )
    (net (code "47") (name "SRC") (class "Default")
      (node (ref "C4") (pin "2") (pinfunction "2_2") (pintype "passive"))
      (node (ref "D5") (pin "2") (pinfunction "A_2") (pintype "bidirectional"))
      (node (ref "L1") (pin "1") (pinfunction "1_1") (pintype "passive"))
      (node (ref "Q3") (pin "3") (pinfunction "D_3") (pintype "bidirectional"))
    )
    (net (code "48") (name "SS_SD") (class "Default")
      (node (ref "D8") (pin "1") (pinfunction "1_1") (pintype "passive"))
      (node (ref "J4") (pin "P2") (pinfunction "CD/DAT3_P2") (pintype "bidirectional"))
      (node (ref "R10") (pin "1") (pinfunction "1_1") (pintype "passive"))
      (node (ref "U2") (pin "4") (pinfunction "IO4_4") (pintype "bidirectional"))
    )
    (net (code "49") (name "TX") (class "Default")
      (node (ref "TP1") (pin "TP") (pinfunction "TP_TP") (pintype "input"))
      (node (ref "U2") (pin "25") (pinfunction "TXD0/GPIO16_25") (pintype "bidirectional"))
    )
    (net (code "50") (name "USB_D+") (class "Default")
      (node (ref "D1") (pin "4") (pinfunction "I/O2_2_4") (pintype "bidirectional"))
      (node (ref "U2") (pin "14") (pinfunction "IO13_14") (pintype "bidirectional"))
    )
    (net (code "51") (name "USB_D-") (class "Default")
      (node (ref "D1") (pin "6") (pinfunction "I/O1_2_6") (pintype "bidirectional"))
      (node (ref "U2") (pin "13") (pinfunction "IO12_13") (pintype "bidirectional"))
    )
    (net (code "52") (name "VBAT") (class "Default")
      (node (ref "C2_BAT") (pin "1") (pinfunction "1_1") (pintype "passive"))
      (node (ref "Q1") (pin "3") (pinfunction "D_3") (pintype "bidirectional"))
      (node (ref "TP3") (pin "TP") (pinfunction "TP_TP") (pintype "input"))
      (node (ref "U10") (pin "3") (pinfunction "VBAT_3") (pintype "power_in"))
      (node (ref "U4") (pin "2") (pinfunction "CELL_2") (pintype "power_in"))
      (node (ref "U4") (pin "3") (pinfunction "VDD_3") (pintype "power_in"))
    )
    (net (code "53") (name "VBUS") (class "Default")
      (node (ref "C1_BAT") (pin "1") (pinfunction "1_1") (pintype "passive"))
      (node (ref "C4_USB") (pin "1") (pinfunction "1_1") (pintype "passive"))
      (node (ref "C5_USB") (pin "1") (pinfunction "1_1") (pintype "passive"))
      (node (ref "CHG_LED") (pin "A") (pinfunction "A_A") (pintype "passive"))
      (node (ref "D1") (pin "2") (pinfunction "GND_2") (pintype "bidirectional"))
      (node (ref "D2") (pin "2") (pinfunction "ANODE_2") (pintype "bidirectional"))
      (node (ref "PFMF.050.1") (pin "2") (pinfunction "2_2") (pintype "passive"))
      (node (ref "Q1") (pin "1") (pinfunction "G_1") (pintype "bidirectional"))
      (node (ref "R1_PWRBUS") (pin "2") (pinfunction "2_2") (pintype "passive"))
      (node (ref "TP14") (pin "TP") (pinfunction "TP_TP") (pintype "input"))
      (node (ref "U10") (pin "4") (pinfunction "VIN_4") (pintype "power_in"))
    )
    (net (code "54") (name "VRTC") (class "Default")
      (node (ref "C10_SUPERCAP") (pin "2") (pinfunction "2_2") (pintype "passive"))
      (node (ref "C8") (pin "1") (pinfunction "1_1") (pintype "passive"))
      (node (ref "R_CAPACITOR") (pin "2") (pinfunction "2_2") (pintype "passive"))
      (node (ref "U3") (pin "14") (pinfunction "VBAT_14") (pintype "power_in"))
    )
    (net (code "55") (name "VUSB") (class "Default")
      (node (ref "J2") (pin "A4") (pinfunction "A4_A4") (pintype "bidirectional"))
      (node (ref "J2") (pin "A9") (pinfunction "A9_A9") (pintype "bidirectional"))
      (node (ref "J2") (pin "B4") (pinfunction "B4_B4") (pintype "bidirectional"))
      (node (ref "J2") (pin "B9") (pinfunction "B9_B9") (pintype "bidirectional"))
      (node (ref "PFMF.050.1") (pin "1") (pinfunction "1_1") (pintype "passive"))
    )
    (net (code "56") (name "unconnected-(IC1-NC-Pad4)") (class "Default")
      (node (ref "IC1") (pin "4") (pinfunction "NC_4") (pintype "no_connect"))
    )
    (net (code "57") (name "unconnected-(IC4-NC-Pad4)") (class "Default")
      (node (ref "IC4") (pin "4") (pinfunction "NC_4") (pintype "no_connect"))
    )
    (net (code "58") (name "unconnected-(J1-Pad1)") (class "Default")
      (node (ref "J1") (pin "1") (pinfunction "1_1") (pintype "bidirectional"))
    )
    (net (code "59") (name "unconnected-(J1-Pad6)") (class "Default")
      (node (ref "J1") (pin "6") (pinfunction "6_6") (pintype "bidirectional"))
    )
    (net (code "60") (name "unconnected-(J1-Pad7)") (class "Default")
      (node (ref "J1") (pin "7") (pinfunction "7_7") (pintype "bidirectional"))
    )
    (net (code "61") (name "unconnected-(J2-PadA8)") (class "Default")
      (node (ref "J2") (pin "A8") (pinfunction "A8_A8") (pintype "bidirectional"))
    )
    (net (code "62") (name "unconnected-(J2-PadB8)") (class "Default")
      (node (ref "J2") (pin "B8") (pinfunction "B8_B8") (pintype "bidirectional"))
    )
    (net (code "63") (name "unconnected-(J4-DAT1-PadP8)") (class "Default")
      (node (ref "J4") (pin "P8") (pinfunction "DAT1_P8") (pintype "bidirectional"))
    )
    (net (code "64") (name "unconnected-(J4-DAT2-PadP1)") (class "Default")
      (node (ref "J4") (pin "P1") (pinfunction "DAT2_P1") (pintype "bidirectional"))
    )
    (net (code "65") (name "unconnected-(J4-DETECTION_1-PadS1)") (class "Default")
      (node (ref "J4") (pin "S1") (pinfunction "DETECTION_1_S1") (pintype "bidirectional"))
    )
    (net (code "66") (name "unconnected-(J4-DETECTION_2-PadS2)") (class "Default")
      (node (ref "J4") (pin "S2") (pinfunction "DETECTION_2_S2") (pintype "bidirectional"))
    )
    (net (code "67") (name "unconnected-(U2-NC-Pad22)") (class "Default")
      (node (ref "U2") (pin "22") (pinfunction "NC_22") (pintype "no_connect"))
    )
    (net (code "68") (name "unconnected-(U4-~{ALERT}-Pad5)") (class "Default")
      (node (ref "U4") (pin "5") (pinfunction "~{ALERT}_5") (pintype "output"))
    )
  )
)
